# mini_lathe_motor_monitor.net
KiCad netlist of a schematic drawn in Altium Designer
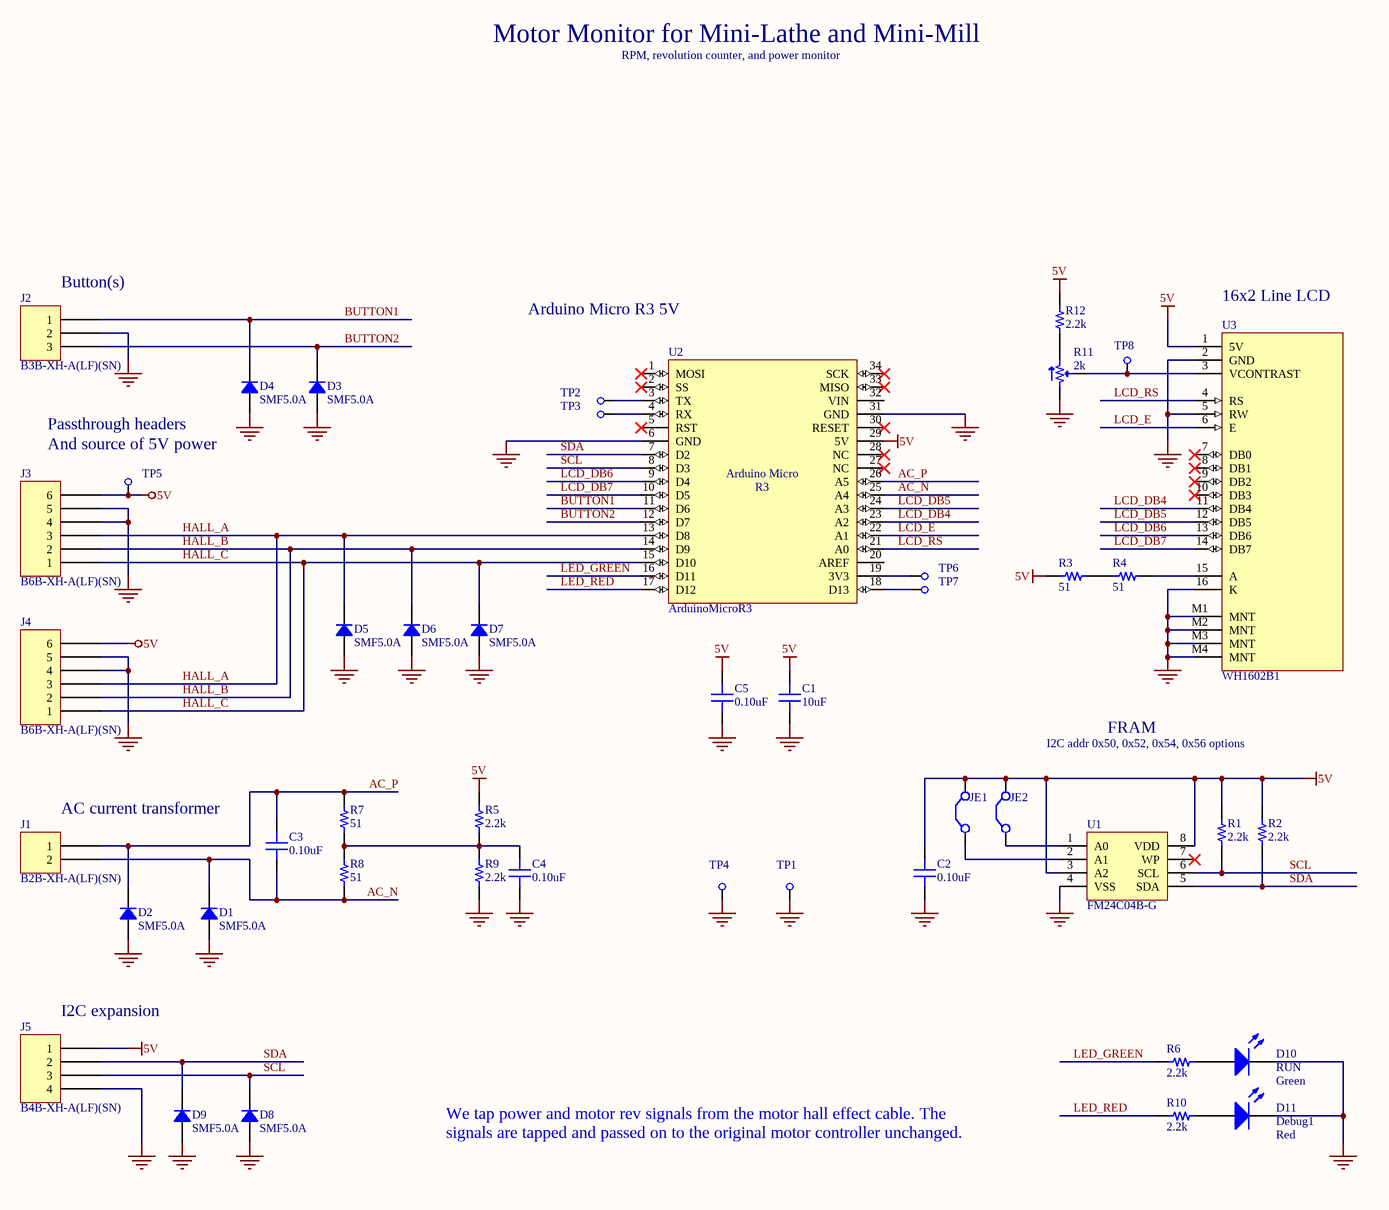
[diagram p0: mini_lathe_motor_monitor.SchDoc]

(export (version "E")
  (design (tool "Eeschema 10.0.6"))
  (components
    (comp (ref "C1")
      (value "10uF")
      (footprint "CAP 0805/2012")
      (description "CAP CER 10UF 10V X7R 0805")
      (fields
        (field (name "PART NUMBER") "GRM21BR71A106KE51L")
        (field (name "MANUFACTURER") "Murata Electronics North America")
      )
      (libsource (lib "CLDB") (part "Capacitor"))
    )
    (comp (ref "C2")
      (value "0.10uF")
      (footprint "CAP 0603/1608")
      (description "CAP CER 0.1UF 16V X7R 0603")
      (fields
        (field (name "PART NUMBER") "GRM188R71C104KA01D")
        (field (name "MANUFACTURER") "Murata Electronics North America")
      )
      (libsource (lib "CLDB") (part "Capacitor"))
    )
    (comp (ref "C3")
      (value "0.10uF")
      (footprint "CAP 0603/1608")
      (description "CAP CER 0.1UF 16V X7R 0603")
      (fields
        (field (name "PART NUMBER") "GRM188R71C104KA01D")
        (field (name "MANUFACTURER") "Murata Electronics North America")
      )
      (libsource (lib "CLDB") (part "Capacitor"))
    )
    (comp (ref "C4")
      (value "0.10uF")
      (footprint "CAP 0603/1608")
      (description "CAP CER 0.1UF 16V X7R 0603")
      (fields
        (field (name "PART NUMBER") "GRM188R71C104KA01D")
        (field (name "MANUFACTURER") "Murata Electronics North America")
      )
      (libsource (lib "CLDB") (part "Capacitor"))
    )
    (comp (ref "C5")
      (value "0.10uF")
      (footprint "CAP 0603/1608")
      (description "CAP CER 0.1UF 16V X7R 0603")
      (fields
        (field (name "PART NUMBER") "GRM188R71C104KA01D")
        (field (name "MANUFACTURER") "Murata Electronics North America")
      )
      (libsource (lib "CLDB") (part "Capacitor"))
    )
    (comp (ref "D1")
      (value "SMF5.0A")
      (footprint "SOD123F")
      (description "TVS DIODE 5VWM 9.2VC SOD123")
      (fields (field (name "MANUFACTURER") "Littelfuse Inc."))
      (libsource (lib "CLDB") (part "Diode"))
    )
    (comp (ref "D2")
      (value "SMF5.0A")
      (footprint "SOD123F")
      (description "TVS DIODE 5VWM 9.2VC SOD123")
      (fields (field (name "MANUFACTURER") "Littelfuse Inc."))
      (libsource (lib "CLDB") (part "Diode"))
    )
    (comp (ref "D3")
      (value "SMF5.0A")
      (footprint "SOD123F")
      (description "TVS DIODE 5VWM 9.2VC SOD123")
      (fields (field (name "MANUFACTURER") "Littelfuse Inc."))
      (libsource (lib "CLDB") (part "Diode"))
    )
    (comp (ref "D4")
      (value "SMF5.0A")
      (footprint "SOD123F")
      (description "TVS DIODE 5VWM 9.2VC SOD123")
      (fields (field (name "MANUFACTURER") "Littelfuse Inc."))
      (libsource (lib "CLDB") (part "Diode"))
    )
    (comp (ref "D5")
      (value "SMF5.0A")
      (footprint "SOD123F")
      (description "TVS DIODE 5VWM 9.2VC SOD123")
      (fields (field (name "MANUFACTURER") "Littelfuse Inc."))
      (libsource (lib "CLDB") (part "Diode"))
    )
    (comp (ref "D6")
      (value "SMF5.0A")
      (footprint "SOD123F")
      (description "TVS DIODE 5VWM 9.2VC SOD123")
      (fields (field (name "MANUFACTURER") "Littelfuse Inc."))
      (libsource (lib "CLDB") (part "Diode"))
    )
    (comp (ref "D7")
      (value "SMF5.0A")
      (footprint "SOD123F")
      (description "TVS DIODE 5VWM 9.2VC SOD123")
      (fields (field (name "MANUFACTURER") "Littelfuse Inc."))
      (libsource (lib "CLDB") (part "Diode"))
    )
    (comp (ref "D8")
      (value "SMF5.0A")
      (footprint "SOD123F")
      (description "TVS DIODE 5VWM 9.2VC SOD123")
      (fields (field (name "MANUFACTURER") "Littelfuse Inc."))
      (libsource (lib "CLDB") (part "Diode"))
    )
    (comp (ref "D9")
      (value "SMF5.0A")
      (footprint "SOD123F")
      (description "TVS DIODE 5VWM 9.2VC SOD123")
      (fields (field (name "MANUFACTURER") "Littelfuse Inc."))
      (libsource (lib "CLDB") (part "Diode"))
    )
    (comp (ref "D10")
      (value "RUN")
      (footprint "0603R-GENERIC")
      (description "Typical RED, GREEN, YELLOW, AMBER GaAs LED")
      (fields
        (field (name "PARTNUMBER") "LTST-C194KGKT")
        (field (name "MANUFACTURER") "Lite-On")
        (field (name "PUBLISHER") "Altium Limited")
      )
      (libsource (lib "Miscellaneous Devices") (part "LED2"))
    )
    (comp (ref "D11")
      (value "Debug1")
      (footprint "0603R-GENERIC")
      (description "Typical RED, GREEN, YELLOW, AMBER GaAs LED")
      (fields
        (field (name "PARTNUMBER") "LS Q976-NR-1")
        (field (name "MANUFACTURER") "Osram")
        (field (name "PUBLISHER") "Altium Limited")
      )
      (libsource (lib "Miscellaneous Devices") (part "LED2"))
    )
    (comp (ref "J1")
      (value "B2B-XH-A(LF)(SN)")
      (footprint "JST XH B2B-XH-A")
      (description "CONN HEADER XH TOP 2POS 2.5MM")
      (fields (field (name "MANUFACTURER") "JST Sales America Inc."))
      (libsource (lib "CLDB") (part "2 Pin"))
    )
    (comp (ref "J2")
      (value "B3B-XH-A(LF)(SN)")
      (footprint "JST XH B3B-XH-A")
      (description "CONN HEADER XH TOP 3POS 2.5MM")
      (fields (field (name "MANUFACTURER") "JST Sales America Inc."))
      (libsource (lib "CLDB") (part "3 Pin"))
    )
    (comp (ref "J3")
      (value "B6B-XH-A(LF)(SN)")
      (footprint "JST XH B6B-XH-A")
      (description "CONN HEADER XH TOP 6POS 2.5MM")
      (fields (field (name "MANUFACTURER") "JST Sales America Inc."))
      (libsource (lib "CLDB") (part "6 Pin"))
    )
    (comp (ref "J4")
      (value "B6B-XH-A(LF)(SN)")
      (footprint "JST XH B6B-XH-A")
      (description "CONN HEADER XH TOP 6POS 2.5MM")
      (fields (field (name "MANUFACTURER") "JST Sales America Inc."))
      (libsource (lib "CLDB") (part "6 Pin"))
    )
    (comp (ref "J5")
      (value "B4B-XH-A(LF)(SN)")
      (footprint "JST XH B4B-XH-A")
      (description "CONN HEADER XH TOP 4POS 2.5MM")
      (fields (field (name "MANUFACTURER") "JST Sales America Inc."))
      (libsource (lib "CLDB") (part "4 Pin"))
    )
    (comp (ref "JE1")
      (value "Jumper")
      (footprint "SOLDER_JUMPER1")
      (description "Jumper Wire")
      (fields (field (name "PUBLISHER") "Altium Limited"))
      (libsource (lib "Miscellaneous Devices") (part "Jumper"))
    )
    (comp (ref "JE2")
      (value "Jumper")
      (footprint "SOLDER_JUMPER1")
      (description "Jumper Wire")
      (fields (field (name "PUBLISHER") "Altium Limited"))
      (libsource (lib "Miscellaneous Devices") (part "Jumper"))
    )
    (comp (ref "R1")
      (value "2.2k")
      (footprint "RES 0603/1608")
      (description "RES SMD 2.2K OHM 5% 1/10W 0603")
      (fields
        (field (name "PART NUMBER") "ERJ-3GEYJ222V")
        (field (name "MANUFACTURER") "Panasonic Electronic Components")
      )
      (libsource (lib "CLDB") (part "Resistor"))
    )
    (comp (ref "R2")
      (value "2.2k")
      (footprint "RES 0603/1608")
      (description "RES SMD 2.2K OHM 5% 1/10W 0603")
      (fields
        (field (name "PART NUMBER") "ERJ-3GEYJ222V")
        (field (name "MANUFACTURER") "Panasonic Electronic Components")
      )
      (libsource (lib "CLDB") (part "Resistor"))
    )
    (comp (ref "R3")
      (value "51")
      (footprint "RES 0603/1608")
      (description "RES SMD 51 OHM 5% 1/4W 0603")
      (fields
        (field (name "PART NUMBER") "ERJ-PA3J510V")
        (field (name "MANUFACTURER") "Panasonic Electronic Components")
      )
      (libsource (lib "CLDB") (part "Resistor"))
    )
    (comp (ref "R4")
      (value "51")
      (footprint "RES 0603/1608")
      (description "RES SMD 51 OHM 5% 1/4W 0603")
      (fields
        (field (name "PART NUMBER") "ERJ-PA3J510V")
        (field (name "MANUFACTURER") "Panasonic Electronic Components")
      )
      (libsource (lib "CLDB") (part "Resistor"))
    )
    (comp (ref "R5")
      (value "2.2k")
      (footprint "RES 0603/1608")
      (description "RES SMD 2.2K OHM 5% 1/10W 0603")
      (fields
        (field (name "PART NUMBER") "ERJ-3GEYJ222V")
        (field (name "MANUFACTURER") "Panasonic Electronic Components")
      )
      (libsource (lib "CLDB") (part "Resistor"))
    )
    (comp (ref "R6")
      (value "2.2k")
      (footprint "RES 0603/1608")
      (description "RES SMD 2.2K OHM 5% 1/10W 0603")
      (fields
        (field (name "PART NUMBER") "ERJ-3GEYJ222V")
        (field (name "MANUFACTURER") "Panasonic Electronic Components")
      )
      (libsource (lib "CLDB") (part "Resistor"))
    )
    (comp (ref "R7")
      (value "51")
      (footprint "RES 0603/1608")
      (description "RES SMD 51 OHM 5% 1/4W 0603")
      (fields
        (field (name "PART NUMBER") "ERJ-PA3J510V")
        (field (name "MANUFACTURER") "Panasonic Electronic Components")
      )
      (libsource (lib "CLDB") (part "Resistor"))
    )
    (comp (ref "R8")
      (value "51")
      (footprint "RES 0603/1608")
      (description "RES SMD 51 OHM 5% 1/4W 0603")
      (fields
        (field (name "PART NUMBER") "ERJ-PA3J510V")
        (field (name "MANUFACTURER") "Panasonic Electronic Components")
      )
      (libsource (lib "CLDB") (part "Resistor"))
    )
    (comp (ref "R9")
      (value "2.2k")
      (footprint "RES 0603/1608")
      (description "RES SMD 2.2K OHM 5% 1/10W 0603")
      (fields
        (field (name "PART NUMBER") "ERJ-3GEYJ222V")
        (field (name "MANUFACTURER") "Panasonic Electronic Components")
      )
      (libsource (lib "CLDB") (part "Resistor"))
    )
    (comp (ref "R10")
      (value "2.2k")
      (footprint "RES 0603/1608")
      (description "RES SMD 2.2K OHM 5% 1/10W 0603")
      (fields
        (field (name "PART NUMBER") "ERJ-3GEYJ222V")
        (field (name "MANUFACTURER") "Panasonic Electronic Components")
      )
      (libsource (lib "CLDB") (part "Resistor"))
    )
    (comp (ref "R11")
      (value "2k")
      (footprint "POT Panasonic EVM")
      (description "TRIMMER 2K OHM 0.15W SMD")
      (fields
        (field (name "PART NUMBER") "EVM-3YSX50B23")
        (field (name "MANUFACTURER") "Panasonic Electronic Components")
      )
      (libsource (lib "CLDB") (part "Potentiometer"))
    )
    (comp (ref "R12")
      (value "2.2k")
      (footprint "RES 0603/1608")
      (description "RES SMD 2.2K OHM 5% 1/10W 0603")
      (fields
        (field (name "PART NUMBER") "ERJ-3GEYJ222V")
        (field (name "MANUFACTURER") "Panasonic Electronic Components")
      )
      (libsource (lib "CLDB") (part "Resistor"))
    )
    (comp (ref "TP1")
      (value "TESTPOINT")
      (footprint "TESTPOINT_ROUND_30MIL")
      (libsource (lib "seiscape2") (part "TESTPOINT"))
    )
    (comp (ref "TP2")
      (value "TESTPOINT")
      (footprint "TESTPOINT_ROUND_30MIL")
      (libsource (lib "seiscape2") (part "TESTPOINT"))
    )
    (comp (ref "TP3")
      (value "TESTPOINT")
      (footprint "TESTPOINT_ROUND_30MIL")
      (libsource (lib "seiscape2") (part "TESTPOINT"))
    )
    (comp (ref "TP4")
      (value "TESTPOINT")
      (footprint "TESTPOINT_ROUND_30MIL")
      (libsource (lib "seiscape2") (part "TESTPOINT"))
    )
    (comp (ref "TP5")
      (value "TESTPOINT")
      (footprint "TESTPOINT_ROUND_30MIL")
      (libsource (lib "seiscape2") (part "TESTPOINT"))
    )
    (comp (ref "TP6")
      (value "TESTPOINT")
      (footprint "TESTPOINT_ROUND_30MIL")
      (libsource (lib "seiscape2") (part "TESTPOINT"))
    )
    (comp (ref "TP7")
      (value "TESTPOINT")
      (footprint "TESTPOINT_ROUND_30MIL")
      (libsource (lib "seiscape2") (part "TESTPOINT"))
    )
    (comp (ref "TP8")
      (value "TESTPOINT")
      (footprint "TESTPOINT_ROUND_30MIL")
      (libsource (lib "seiscape2") (part "TESTPOINT"))
    )
    (comp (ref "U1")
      (value "FM24C04B-G")
      (footprint "SO8_N")
      (description "FM24C04B FRAM")
      (fields (field (name "MANUFACTURER") "Cypress"))
      (libsource (lib "mini_lathe_motor_monitor") (part "CAT24C256"))
    )
    (comp (ref "U2")
      (value "ArduinoMicroR3")
      (footprint "ARDUINO_MICRO_R3")
      (description "Arduino Micro R3")
      (fields (field (name "MANUFACTURER") "Arduino") (field (name "PARTNUMBER") "Micro R3"))
      (libsource (lib "mini_lathe_motor_monitor") (part "ArduinoMicroR3"))
    )
    (comp (ref "U3")
      (value "WH1602B1")
      (description "2x16 LCD")
      (fields (field (name "MANUFACTURER") "Winstar"))
      (libsource (lib "mini_lathe_motor_monitor") (part "LCD"))
    )
  )
  (nets
    (net (code "1") (name "/AC_N") (class "Default")
      (node (ref "C3") (pin "1") (pinfunction "1_1") (pintype "passive"))
      (node (ref "D1") (pin "2") (pinfunction "2_2") (pintype "passive"))
      (node (ref "J1") (pin "2") (pinfunction "2_2") (pintype "passive"))
      (node (ref "R8") (pin "2") (pinfunction "2_2") (pintype "passive"))
      (node (ref "U2") (pin "25") (pinfunction "A4_25") (pintype "bidirectional"))
    )
    (net (code "2") (name "/AC_P") (class "Default")
      (node (ref "C3") (pin "2") (pinfunction "2_2") (pintype "passive"))
      (node (ref "D2") (pin "2") (pinfunction "2_2") (pintype "passive"))
      (node (ref "J1") (pin "1") (pinfunction "1_1") (pintype "passive"))
      (node (ref "R7") (pin "1") (pinfunction "1_1") (pintype "passive"))
      (node (ref "U2") (pin "26") (pinfunction "A5_26") (pintype "bidirectional"))
    )
    (net (code "3") (name "/BUTTON1") (class "Default")
      (node (ref "D4") (pin "2") (pinfunction "2_2") (pintype "passive"))
      (node (ref "J2") (pin "1") (pinfunction "1_1") (pintype "passive"))
      (node (ref "U2") (pin "11") (pinfunction "D6_11") (pintype "bidirectional"))
    )
    (net (code "4") (name "/BUTTON2") (class "Default")
      (node (ref "D3") (pin "2") (pinfunction "2_2") (pintype "passive"))
      (node (ref "J2") (pin "3") (pinfunction "3_3") (pintype "passive"))
      (node (ref "U2") (pin "12") (pinfunction "D7_12") (pintype "bidirectional"))
    )
    (net (code "5") (name "/HALL_A") (class "Default")
      (node (ref "D5") (pin "2") (pinfunction "2_2") (pintype "passive"))
      (node (ref "J3") (pin "3") (pinfunction "3_3") (pintype "passive"))
      (node (ref "J4") (pin "3") (pinfunction "3_3") (pintype "passive"))
      (node (ref "U2") (pin "13") (pinfunction "D8_13") (pintype "bidirectional"))
    )
    (net (code "6") (name "/HALL_B") (class "Default")
      (node (ref "D6") (pin "2") (pinfunction "2_2") (pintype "passive"))
      (node (ref "J3") (pin "2") (pinfunction "2_2") (pintype "passive"))
      (node (ref "J4") (pin "2") (pinfunction "2_2") (pintype "passive"))
      (node (ref "U2") (pin "14") (pinfunction "D9_14") (pintype "bidirectional"))
    )
    (net (code "7") (name "/HALL_C") (class "Default")
      (node (ref "D7") (pin "2") (pinfunction "2_2") (pintype "passive"))
      (node (ref "J3") (pin "1") (pinfunction "1_1") (pintype "passive"))
      (node (ref "J4") (pin "1") (pinfunction "1_1") (pintype "passive"))
      (node (ref "U2") (pin "15") (pinfunction "D10_15") (pintype "bidirectional"))
    )
    (net (code "8") (name "/LCD_DB4") (class "Default")
      (node (ref "U2") (pin "23") (pinfunction "A2_23") (pintype "bidirectional"))
      (node (ref "U3") (pin "11") (pinfunction "DB4_11") (pintype "bidirectional"))
    )
    (net (code "9") (name "/LCD_DB5") (class "Default")
      (node (ref "U2") (pin "24") (pinfunction "A3_24") (pintype "bidirectional"))
      (node (ref "U3") (pin "12") (pinfunction "DB5_12") (pintype "bidirectional"))
    )
    (net (code "10") (name "/LCD_DB6") (class "Default")
      (node (ref "U2") (pin "9") (pinfunction "D4_9") (pintype "bidirectional"))
      (node (ref "U3") (pin "13") (pinfunction "DB6_13") (pintype "bidirectional"))
    )
    (net (code "11") (name "/LCD_DB7") (class "Default")
      (node (ref "U2") (pin "10") (pinfunction "D5_10") (pintype "bidirectional"))
      (node (ref "U3") (pin "14") (pinfunction "DB7_14") (pintype "bidirectional"))
    )
    (net (code "12") (name "/LCD_E") (class "Default")
      (node (ref "U2") (pin "22") (pinfunction "A1_22") (pintype "bidirectional"))
      (node (ref "U3") (pin "6") (pinfunction "E_6") (pintype "input"))
    )
    (net (code "13") (name "/LCD_RS") (class "Default")
      (node (ref "U2") (pin "21") (pinfunction "A0_21") (pintype "bidirectional"))
      (node (ref "U3") (pin "4") (pinfunction "RS_4") (pintype "input"))
    )
    (net (code "14") (name "/LED_GREEN") (class "Default")
      (node (ref "R6") (pin "1") (pinfunction "1_1") (pintype "passive"))
      (node (ref "U2") (pin "16") (pinfunction "D11_16") (pintype "bidirectional"))
    )
    (net (code "15") (name "/LED_RED") (class "Default")
      (node (ref "R10") (pin "1") (pinfunction "1_1") (pintype "passive"))
      (node (ref "U2") (pin "17") (pinfunction "D12_17") (pintype "bidirectional"))
    )
    (net (code "16") (name "/SCL") (class "Default")
      (node (ref "D8") (pin "2") (pinfunction "2_2") (pintype "passive"))
      (node (ref "J5") (pin "3") (pinfunction "3_3") (pintype "passive"))
      (node (ref "R1") (pin "2") (pinfunction "2_2") (pintype "passive"))
      (node (ref "U1") (pin "6") (pinfunction "SCL_6") (pintype "passive"))
      (node (ref "U2") (pin "8") (pinfunction "D3_8") (pintype "bidirectional"))
    )
    (net (code "17") (name "/SDA") (class "Default")
      (node (ref "D9") (pin "2") (pinfunction "2_2") (pintype "passive"))
      (node (ref "J5") (pin "2") (pinfunction "2_2") (pintype "passive"))
      (node (ref "R2") (pin "2") (pinfunction "2_2") (pintype "passive"))
      (node (ref "U1") (pin "5") (pinfunction "SDA_5") (pintype "passive"))
      (node (ref "U2") (pin "7") (pinfunction "D2_7") (pintype "bidirectional"))
    )
    (net (code "18") (name "5V") (class "Default")
      (node (ref "C1") (pin "1") (pinfunction "1_1") (pintype "passive"))
      (node (ref "C2") (pin "2") (pinfunction "2_2") (pintype "passive"))
      (node (ref "C5") (pin "2") (pinfunction "2_2") (pintype "passive"))
      (node (ref "J3") (pin "6") (pinfunction "6_6") (pintype "passive"))
      (node (ref "J4") (pin "6") (pinfunction "6_6") (pintype "passive"))
      (node (ref "J5") (pin "1") (pinfunction "1_1") (pintype "passive"))
      (node (ref "JE1") (pin "2") (pinfunction "C2_2") (pintype "passive"))
      (node (ref "JE2") (pin "2") (pinfunction "C2_2") (pintype "passive"))
      (node (ref "R1") (pin "1") (pinfunction "1_1") (pintype "passive"))
      (node (ref "R12") (pin "1") (pinfunction "1_1") (pintype "passive"))
      (node (ref "R2") (pin "1") (pinfunction "1_1") (pintype "passive"))
      (node (ref "R3") (pin "1") (pinfunction "1_1") (pintype "passive"))
      (node (ref "R5") (pin "1") (pinfunction "1_1") (pintype "passive"))
      (node (ref "TP5") (pin "1") (pintype "passive"))
      (node (ref "U1") (pin "3") (pinfunction "A2_3") (pintype "passive"))
      (node (ref "U1") (pin "8") (pinfunction "VDD_8") (pintype "passive"))
      (node (ref "U2") (pin "29") (pinfunction "5V_29") (pintype "power_in"))
      (node (ref "U3") (pin "1") (pinfunction "5V_1") (pintype "power_in"))
    )
    (net (code "19") (name "GND") (class "Default")
      (node (ref "C1") (pin "2") (pinfunction "2_2") (pintype "passive"))
      (node (ref "C2") (pin "1") (pinfunction "1_1") (pintype "passive"))
      (node (ref "C4") (pin "1") (pinfunction "1_1") (pintype "passive"))
      (node (ref "C5") (pin "1") (pinfunction "1_1") (pintype "passive"))
      (node (ref "D1") (pin "1") (pinfunction "1_1") (pintype "passive"))
      (node (ref "D10") (pin "2") (pinfunction "K_2") (pintype "passive"))
      (node (ref "D11") (pin "2") (pinfunction "K_2") (pintype "passive"))
      (node (ref "D2") (pin "1") (pinfunction "1_1") (pintype "passive"))
      (node (ref "D3") (pin "1") (pinfunction "1_1") (pintype "passive"))
      (node (ref "D4") (pin "1") (pinfunction "1_1") (pintype "passive"))
      (node (ref "D5") (pin "1") (pinfunction "1_1") (pintype "passive"))
      (node (ref "D6") (pin "1") (pinfunction "1_1") (pintype "passive"))
      (node (ref "D7") (pin "1") (pinfunction "1_1") (pintype "passive"))
      (node (ref "D8") (pin "1") (pinfunction "1_1") (pintype "passive"))
      (node (ref "D9") (pin "1") (pinfunction "1_1") (pintype "passive"))
      (node (ref "J2") (pin "2") (pinfunction "2_2") (pintype "passive"))
      (node (ref "J3") (pin "4") (pinfunction "4_4") (pintype "passive"))
      (node (ref "J3") (pin "5") (pinfunction "5_5") (pintype "passive"))
      (node (ref "J4") (pin "4") (pinfunction "4_4") (pintype "passive"))
      (node (ref "J4") (pin "5") (pinfunction "5_5") (pintype "passive"))
      (node (ref "J5") (pin "4") (pinfunction "4_4") (pintype "passive"))
      (node (ref "R11") (pin "1") (pinfunction "1_1") (pintype "passive"))
      (node (ref "R9") (pin "2") (pinfunction "2_2") (pintype "passive"))
      (node (ref "TP1") (pin "1") (pintype "passive"))
      (node (ref "TP4") (pin "1") (pintype "passive"))
      (node (ref "U1") (pin "4") (pinfunction "VSS_4") (pintype "passive"))
      (node (ref "U2") (pin "31") (pinfunction "GND_31") (pintype "power_in"))
      (node (ref "U2") (pin "6") (pinfunction "GND_6") (pintype "power_in"))
      (node (ref "U3") (pin "16") (pinfunction "K_16") (pintype "passive"))
      (node (ref "U3") (pin "2") (pinfunction "GND_2") (pintype "power_in"))
      (node (ref "U3") (pin "5") (pinfunction "RW_5") (pintype "input"))
      (node (ref "U3") (pin "M1") (pinfunction "MNT_M1") (pintype "passive"))
      (node (ref "U3") (pin "M2") (pinfunction "MNT_M2") (pintype "passive"))
      (node (ref "U3") (pin "M3") (pinfunction "MNT_M3") (pintype "passive"))
      (node (ref "U3") (pin "M4") (pinfunction "MNT_M4") (pintype "passive"))
    )
    (net (code "20") (name "Net-(C4-Pad2)") (class "Default")
      (node (ref "C4") (pin "2") (pinfunction "2_2") (pintype "passive"))
      (node (ref "R5") (pin "2") (pinfunction "2_2") (pintype "passive"))
      (node (ref "R7") (pin "2") (pinfunction "2_2") (pintype "passive"))
      (node (ref "R8") (pin "1") (pinfunction "1_1") (pintype "passive"))
      (node (ref "R9") (pin "1") (pinfunction "1_1") (pintype "passive"))
    )
    (net (code "21") (name "Net-(D10-A)") (class "Default")
      (node (ref "D10") (pin "1") (pinfunction "A_1") (pintype "passive"))
      (node (ref "R6") (pin "2") (pinfunction "2_2") (pintype "passive"))
    )
    (net (code "22") (name "Net-(D11-A)") (class "Default")
      (node (ref "D11") (pin "1") (pinfunction "A_1") (pintype "passive"))
      (node (ref "R10") (pin "2") (pinfunction "2_2") (pintype "passive"))
    )
    (net (code "23") (name "Net-(JE1-C1)") (class "Default")
      (node (ref "JE1") (pin "1") (pinfunction "C1_1") (pintype "passive"))
      (node (ref "U1") (pin "2") (pinfunction "A1_2") (pintype "passive"))
    )
    (net (code "24") (name "Net-(JE2-C1)") (class "Default")
      (node (ref "JE2") (pin "1") (pinfunction "C1_1") (pintype "passive"))
      (node (ref "U1") (pin "1") (pinfunction "A0_1") (pintype "passive"))
    )
    (net (code "25") (name "Net-(R3-Pad2)") (class "Default")
      (node (ref "R3") (pin "2") (pinfunction "2_2") (pintype "passive"))
      (node (ref "R4") (pin "1") (pinfunction "1_1") (pintype "passive"))
    )
    (net (code "26") (name "Net-(R11-Pad3)") (class "Default")
      (node (ref "R11") (pin "3") (pinfunction "3_3") (pintype "passive"))
      (node (ref "R12") (pin "2") (pinfunction "2_2") (pintype "passive"))
    )
    (net (code "27") (name "Net-(U2-3V3)") (class "Default")
      (node (ref "TP6") (pin "1") (pintype "passive"))
      (node (ref "U2") (pin "19") (pinfunction "3V3_19") (pintype "power_in"))
    )
    (net (code "28") (name "Net-(U2-D13)") (class "Default")
      (node (ref "TP7") (pin "1") (pintype "passive"))
      (node (ref "U2") (pin "18") (pinfunction "D13_18") (pintype "bidirectional"))
    )
    (net (code "29") (name "Net-(U2-RX)") (class "Default")
      (node (ref "TP3") (pin "1") (pintype "passive"))
      (node (ref "U2") (pin "4") (pinfunction "RX_4") (pintype "bidirectional"))
    )
    (net (code "30") (name "Net-(U2-TX)") (class "Default")
      (node (ref "TP2") (pin "1") (pintype "passive"))
      (node (ref "U2") (pin "3") (pinfunction "TX_3") (pintype "bidirectional"))
    )
    (net (code "31") (name "Net-(U3-A)") (class "Default")
      (node (ref "R4") (pin "2") (pinfunction "2_2") (pintype "passive"))
      (node (ref "U3") (pin "15") (pinfunction "A_15") (pintype "passive"))
    )
    (net (code "32") (name "Net-(U3-VCONTRAST)") (class "Default")
      (node (ref "R11") (pin "2") (pinfunction "2_2") (pintype "passive"))
      (node (ref "TP8") (pin "1") (pintype "passive"))
      (node (ref "U3") (pin "3") (pinfunction "VCONTRAST_3") (pintype "power_in"))
    )
    (net (code "33") (name "unconnected-(U1-WP-Pad7)") (class "Default")
      (node (ref "U1") (pin "7") (pinfunction "WP_7") (pintype "passive+no_connect"))
    )
    (net (code "34") (name "unconnected-(U2-AREF-Pad20)") (class "Default")
      (node (ref "U2") (pin "20") (pinfunction "AREF_20") (pintype "passive"))
    )
    (net (code "35") (name "unconnected-(U2-MISO-Pad33)") (class "Default")
      (node (ref "U2") (pin "33") (pinfunction "MISO_33") (pintype "bidirectional+no_connect"))
    )
    (net (code "36") (name "unconnected-(U2-MOSI-Pad1)") (class "Default")
      (node (ref "U2") (pin "1") (pinfunction "MOSI_1") (pintype "bidirectional+no_connect"))
    )
    (net (code "37") (name "unconnected-(U2-NC-Pad27)") (class "Default")
      (node (ref "U2") (pin "27") (pinfunction "NC_27") (pintype "passive+no_connect"))
    )
    (net (code "38") (name "unconnected-(U2-NC-Pad28)") (class "Default")
      (node (ref "U2") (pin "28") (pinfunction "NC_28") (pintype "passive+no_connect"))
    )
    (net (code "39") (name "unconnected-(U2-RESET-Pad30)") (class "Default")
      (node (ref "U2") (pin "30") (pinfunction "RESET_30") (pintype "power_in+no_connect"))
    )
    (net (code "40") (name "unconnected-(U2-RST-Pad5)") (class "Default")
      (node (ref "U2") (pin "5") (pinfunction "RST_5") (pintype "passive+no_connect"))
    )
    (net (code "41") (name "unconnected-(U2-SCK-Pad34)") (class "Default")
      (node (ref "U2") (pin "34") (pinfunction "SCK_34") (pintype "bidirectional+no_connect"))
    )
    (net (code "42") (name "unconnected-(U2-SS-Pad2)") (class "Default")
      (node (ref "U2") (pin "2") (pinfunction "SS_2") (pintype "bidirectional+no_connect"))
    )
    (net (code "43") (name "unconnected-(U2-VIN-Pad32)") (class "Default")
      (node (ref "U2") (pin "32") (pinfunction "VIN_32") (pintype "power_in"))
    )
    (net (code "44") (name "unconnected-(U3-DB0-Pad7)") (class "Default")
      (node (ref "U3") (pin "7") (pinfunction "DB0_7") (pintype "bidirectional+no_connect"))
    )
    (net (code "45") (name "unconnected-(U3-DB1-Pad8)") (class "Default")
      (node (ref "U3") (pin "8") (pinfunction "DB1_8") (pintype "bidirectional+no_connect"))
    )
    (net (code "46") (name "unconnected-(U3-DB2-Pad9)") (class "Default")
      (node (ref "U3") (pin "9") (pinfunction "DB2_9") (pintype "bidirectional+no_connect"))
    )
    (net (code "47") (name "unconnected-(U3-DB3-Pad10)") (class "Default")
      (node (ref "U3") (pin "10") (pinfunction "DB3_10") (pintype "bidirectional+no_connect"))
    )
  )
)
